# LM2587.net
KiCad netlist of a schematic drawn in Altium Designer
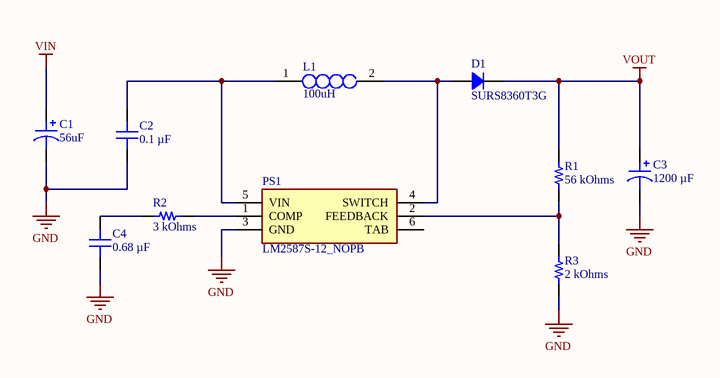
[diagram p0: LM2587.SchDoc]

(export (version "E")
  (design (tool "Eeschema 10.0.6"))
  (components
    (comp (ref "C1")
      (value "56uF")
      (footprint "CAP ALSMD 8.3MM H10.5MM")
      (description "CAP ALUM 1200UF 20% 6.3V SMD")
      (fields (field (name "PART NUMBER") "6.3TPV1200M8X10.5") (field (name "MANUFACTURER") "Rubycon"))
      (libsource (lib "Celestial Altium Library - altium_library") (part "Polarised Capacitor"))
    )
    (comp (ref "C2")
      (value "0.1 µF")
      (footprint "CAP 0805_2012")
      (description "CAP CER 0.1UF 50V X7R 0805")
      (fields (field (name "PART NUMBER") "CC0805MRX7R9BB104") (field (name "MANUFACTURER") "Yageo"))
      (libsource (lib "Celestial Altium Library - altium_library") (part "Capacitor"))
    )
    (comp (ref "C3")
      (value "1200 µF")
      (footprint "CAP ALSMD 8.3MM H10.5MM")
      (description "CAP ALUM 1200UF 20% 6.3V SMD")
      (fields (field (name "PART NUMBER") "6.3TPV1200M8X10.5") (field (name "MANUFACTURER") "Rubycon"))
      (libsource (lib "Celestial Altium Library - altium_library") (part "Polarised Capacitor"))
    )
    (comp (ref "C4")
      (value "0.68 µF")
      (footprint "CAP 0805_2012")
      (description "CAP CER 0.68UF 50V X7R 0805")
      (fields
        (field (name "PART NUMBER") "CGA4J3X7R1H684K125AB")
        (field (name "MANUFACTURER") "TDK Corporation")
      )
      (libsource (lib "Celestial Altium Library - altium_library") (part "Capacitor"))
    )
    (comp (ref "D1")
      (value "SURS8360T3G")
      (footprint "DO214AB SMC")
      (description "DIODE GEN PURP 600V 3A SMC")
      (fields (field (name "MANUFACTURER") "ON Semiconductor"))
      (libsource (lib "Celestial Altium Library - altium_library") (part "Diode"))
    )
    (comp (ref "L1")
      (value "100uH")
      (footprint "SamacSys:2100LL1R0VRC")
      (description "Inductor")
      (fields
        (field (name "MANUFACTURER_PART_NUMBER") "2100LL-1R0-V-RC")
        (field (name "MOUSER PART NUMBER") "652-2100LL-1R0-V-RC")
      )
      (libsource (lib "*") (part "2100LL-1R0-V-RC"))
    )
    (comp (ref "PS1")
      (value "LM2587S-12_NOPB")
      (footprint "SamacSys:KTT0005B")
      (description "Texas Instruments LM2587S-12/NOPB")
      (fields (field (name "MANUFACTURER_PART_NUMBER") "LM2587S-12/NOPB"))
      (libsource (lib "SamacSys") (part "LM2587S-12_NOPB"))
    )
    (comp (ref "R1")
      (value "56 kOhms")
      (footprint "RES 0805_2012")
      (description "RES 56K OHM 1% 1/8W 0805")
      (fields
        (field (name "PART NUMBER") "RMCF0805FT56K0")
        (field (name "MANUFACTURER") "Stackpole Electronics Inc")
      )
      (libsource (lib "Celestial Altium Library - altium_library") (part "Resistor"))
    )
    (comp (ref "R2")
      (value "3 kOhms")
      (footprint "RES 0805_2012")
      (description "RES SMD 3K OHM 1% 1/8W 0805")
      (fields
        (field (name "PART NUMBER") "ERJ-6ENF3001V")
        (field (name "MANUFACTURER") "Panasonic Electronic Components")
      )
      (libsource (lib "Celestial Altium Library - altium_library") (part "Resistor"))
    )
    (comp (ref "R3")
      (value "2 kOhms")
      (footprint "RES 0805_2012")
      (description "RES SMD 2K OHM 1% 1/2W 0805")
      (fields (field (name "PART NUMBER") "RCS08052K00FKEA") (field (name "MANUFACTURER") "Vishay Dale"))
      (libsource (lib "Celestial Altium Library - altium_library") (part "Resistor"))
    )
  )
  (nets
    (net (code "1") (name "GND") (class "Default")
      (node (ref "C1") (pin "2") (pinfunction "2_2") (pintype "passive"))
      (node (ref "C2") (pin "1") (pinfunction "1_1") (pintype "passive"))
      (node (ref "C3") (pin "2") (pinfunction "2_2") (pintype "passive"))
      (node (ref "C4") (pin "1") (pinfunction "1_1") (pintype "passive"))
      (node (ref "PS1") (pin "3") (pinfunction "GND_3") (pintype "passive"))
      (node (ref "R3") (pin "1") (pinfunction "1_1") (pintype "passive"))
    )
    (net (code "2") (name "Net-(C4-Pad2)") (class "Default")
      (node (ref "C4") (pin "2") (pinfunction "2_2") (pintype "passive"))
      (node (ref "R2") (pin "1") (pinfunction "1_1") (pintype "passive"))
    )
    (net (code "3") (name "Net-(PS1-COMP)") (class "Default")
      (node (ref "PS1") (pin "1") (pinfunction "COMP_1") (pintype "passive"))
      (node (ref "R2") (pin "2") (pinfunction "2_2") (pintype "passive"))
    )
    (net (code "4") (name "Net-(PS1-FEEDBACK)") (class "Default")
      (node (ref "PS1") (pin "2") (pinfunction "FEEDBACK_2") (pintype "passive"))
      (node (ref "R1") (pin "1") (pinfunction "1_1") (pintype "passive"))
      (node (ref "R3") (pin "2") (pinfunction "2_2") (pintype "passive"))
    )
    (net (code "5") (name "Net-(PS1-SWITCH)") (class "Default")
      (node (ref "D1") (pin "1") (pinfunction "1_1") (pintype "passive"))
      (node (ref "L1") (pin "2") (pinfunction "2_2") (pintype "passive"))
      (node (ref "PS1") (pin "4") (pinfunction "SWITCH_4") (pintype "passive"))
    )
    (net (code "6") (name "Net-(PS1-VIN)") (class "Default")
      (node (ref "C2") (pin "2") (pinfunction "2_2") (pintype "passive"))
      (node (ref "L1") (pin "1") (pinfunction "1_1") (pintype "passive"))
      (node (ref "PS1") (pin "5") (pinfunction "VIN_5") (pintype "passive"))
    )
    (net (code "7") (name "VIN") (class "Default")
      (node (ref "C1") (pin "1") (pinfunction "1_1") (pintype "passive"))
    )
    (net (code "8") (name "VOUT") (class "Default")
      (node (ref "C3") (pin "1") (pinfunction "1_1") (pintype "passive"))
      (node (ref "D1") (pin "2") (pinfunction "2_2") (pintype "passive"))
      (node (ref "R1") (pin "2") (pinfunction "2_2") (pintype "passive"))
    )
    (net (code "9") (name "unconnected-(PS1-TAB-Pad6)") (class "Default")
      (node (ref "PS1") (pin "6") (pinfunction "TAB_6") (pintype "passive"))
    )
  )
)
